# bop_it_sch.net
KiCad netlist of a schematic drawn in Altium Designer
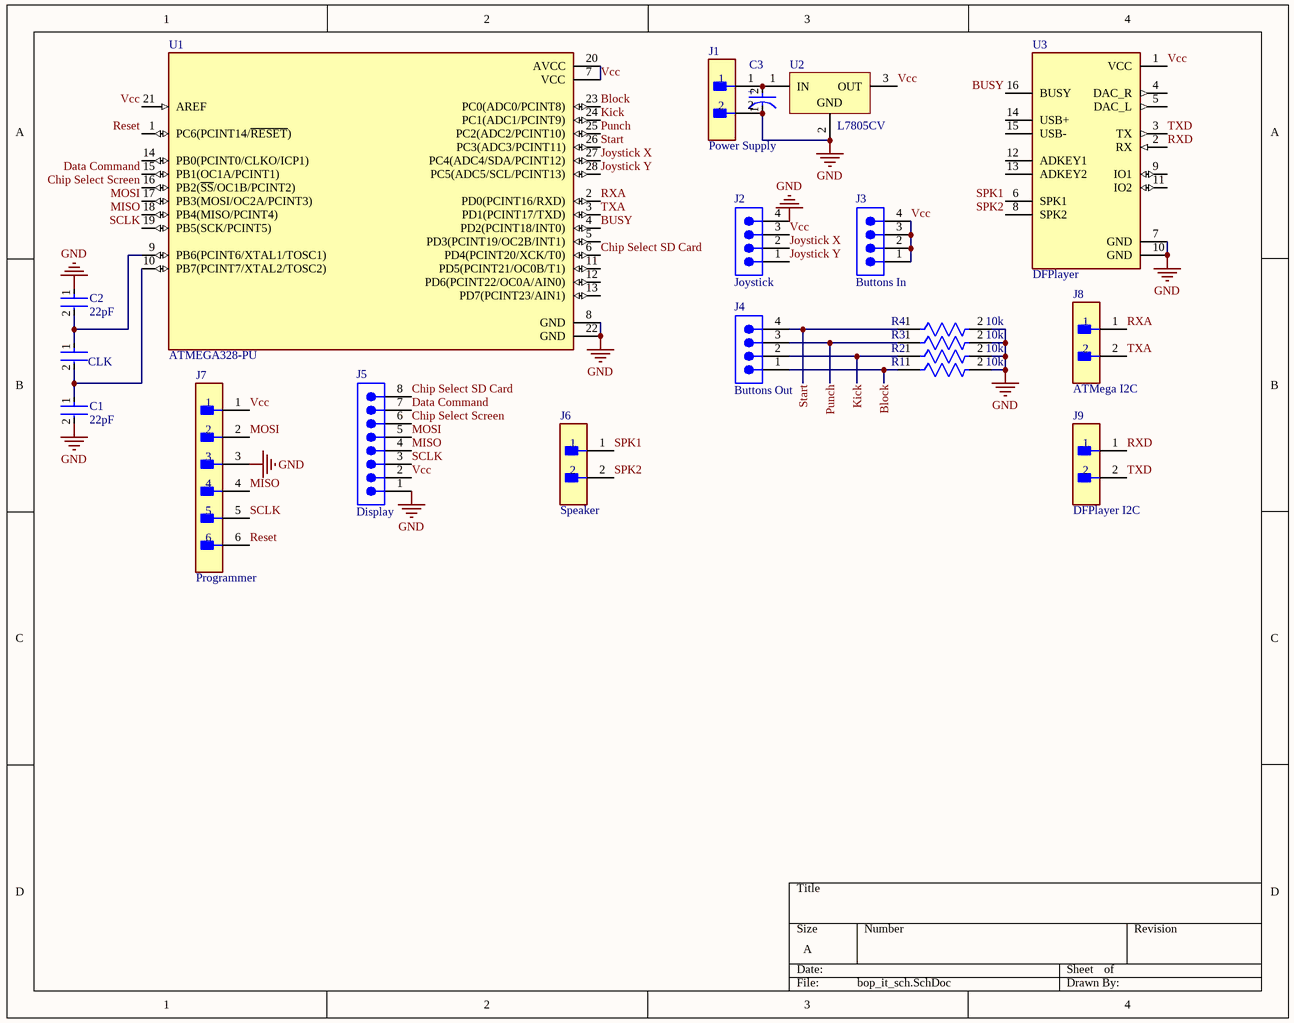
[diagram p0: bop_it_sch.SchDoc]

(export (version "E")
  (design (tool "Eeschema 10.0.6"))
  (components
    (comp (ref "C1")
      (value "22pF")
      (footprint "FP-RDE0M1-MFG")
      (description "Ceramic Capacitor 10nF ±10% 50V X7R Radial")
      (fields (field (name "TOLERANCE") "10%"))
      (libsource (lib "Altium Content Vault") (part "b4654b650e69147ec39a6b967a45e02"))
    )
    (comp (ref "C2")
      (value "22pF")
      (footprint "FP-RDE0M1-MFG")
      (description "Ceramic Capacitor 10nF ±10% 50V X7R Radial")
      (fields (field (name "TOLERANCE") "10%"))
      (libsource (lib "Altium Content Vault") (part "b4654b650e69147ec39a6b967a45e02"))
    )
    (comp (ref "C3")
      (value "~")
      (footprint "FP-RAD-TH-D_5_0_5-L_11_1-MFG")
      (description "Aluminum Electrolytic Capacitors (Radial Lead Type) 1uF ±20% 50V")
      (fields (field (name "TOLERANCE") "20%"))
      (libsource (lib "Altium Content Vault") (part "a00bbbee19879c290e62620ae7e47b1"))
    )
    (comp (ref "CLK")
      (value "~")
      (footprint "FP-RDE0M1-MFG")
      (description "Ceramic Capacitor 10nF ±10% 50V X7R Radial")
      (fields (field (name "TOLERANCE") "10%"))
      (libsource (lib "Altium Content Vault") (part "b4654b650e69147ec39a6b967a45e02"))
    )
    (comp (ref "J1")
      (value "Power Supply")
      (footprint "FP-M20-9990246-MFG")
      (description "CONN HEADER VERT 2POS 2.54MM")
      (fields
        (field (name "OCTOPART") "https://octopart.com/m20-9990246-harwin-2590635")
        (field (name "MANUFACTURER") "Harwin")
      )
      (libsource (lib "Altium Content Vault") (part "3bc925449376181038e59eaffc5286c"))
    )
    (comp (ref "J2")
      (value "Joystick")
      (footprint "61300411121")
      (libsource (lib "Altium Content Vault") (part "Header_Male_1R_04P"))
    )
    (comp (ref "J3")
      (value "Buttons In")
      (footprint "61300411121")
      (libsource (lib "Altium Content Vault") (part "Header_Male_1R_04P"))
    )
    (comp (ref "J4")
      (value "Buttons Out")
      (footprint "61300411121")
      (libsource (lib "Altium Content Vault") (part "Header_Male_1R_04P"))
    )
    (comp (ref "J5")
      (value "Display")
      (footprint "61300811121")
      (libsource (lib "Altium Content Vault") (part "Header_Male_1R_08P"))
    )
    (comp (ref "J6")
      (value "Speaker")
      (footprint "FP-M20-9990246-MFG")
      (description "CONN HEADER VERT 2POS 2.54MM")
      (fields
        (field (name "OCTOPART") "https://octopart.com/m20-9990246-harwin-2590635")
        (field (name "MANUFACTURER") "Harwin")
      )
      (libsource (lib "Altium Content Vault") (part "3bc925449376181038e59eaffc5286c"))
    )
    (comp (ref "J7")
      (value "Programmer")
      (footprint "FP-22-28-4060-MFG")
      (description "CONN HEADER VERT 6POS 2.54MM")
      (libsource (lib "Altium Content Vault") (part "f2cb566baf1c37ab5a3b8e90bbeafd6"))
    )
    (comp (ref "J8")
      (value "ATMega I2C")
      (footprint "FP-M20-9990246-MFG")
      (description "CONN HEADER VERT 2POS 2.54MM")
      (fields
        (field (name "OCTOPART") "https://octopart.com/m20-9990246-harwin-2590635")
        (field (name "MANUFACTURER") "Harwin")
      )
      (libsource (lib "Altium Content Vault") (part "3bc925449376181038e59eaffc5286c"))
    )
    (comp (ref "J9")
      (value "DFPlayer I2C")
      (footprint "FP-M20-9990246-MFG")
      (description "CONN HEADER VERT 2POS 2.54MM")
      (fields
        (field (name "OCTOPART") "https://octopart.com/m20-9990246-harwin-2590635")
        (field (name "MANUFACTURER") "Harwin")
      )
      (libsource (lib "Altium Content Vault") (part "3bc925449376181038e59eaffc5286c"))
    )
    (comp (ref "R1")
      (value "10k")
      (footprint "FP-MBB0207-MFG")
      (description "RES 10K OHM 0.6W 1% AXIAL")
      (fields (field (name "TOLERANCE") "1%"))
      (libsource (lib "Altium Content Vault") (part "1029c3af85768c4190bb7ad29bc67b5"))
    )
    (comp (ref "R2")
      (value "10k")
      (footprint "FP-MBB0207-MFG")
      (description "RES 10K OHM 0.6W 1% AXIAL")
      (fields (field (name "TOLERANCE") "1%"))
      (libsource (lib "Altium Content Vault") (part "1029c3af85768c4190bb7ad29bc67b5"))
    )
    (comp (ref "R3")
      (value "10k")
      (footprint "FP-MBB0207-MFG")
      (description "RES 10K OHM 0.6W 1% AXIAL")
      (fields (field (name "TOLERANCE") "1%"))
      (libsource (lib "Altium Content Vault") (part "1029c3af85768c4190bb7ad29bc67b5"))
    )
    (comp (ref "R4")
      (value "10k")
      (footprint "FP-MBB0207-MFG")
      (description "RES 10K OHM 0.6W 1% AXIAL")
      (fields (field (name "TOLERANCE") "1%"))
      (libsource (lib "Altium Content Vault") (part "1029c3af85768c4190bb7ad29bc67b5"))
    )
    (comp (ref "U1")
      (value "ATMEGA328-PU")
      (footprint "DIP787W46P254L3467H508Q28")
      (description "AVR AVRÂ® ATmega Microcontroller IC 8-Bit 20MHz 32KB (16K x 16) FLASH 28-PDIP")
      (fields (field (name "MF") "Microchip"))
      (libsource (lib "ATMEGA328-PU") (part "ATMEGA328-PU"))
    )
    (comp (ref "U2")
      (value "L7805CV")
      (footprint "TO220FP")
      (description "Positive Voltage Regulator, 5V, 3-Pin TO-220FP")
      (libsource (lib "Altium Content Vault") (part "PM-REG-L4940-SIL3"))
    )
    (comp (ref "U3")
      (value "DFPlayer")
      (footprint "MODULE_DFR0299")
      (description "- MP3 Player Audio Arduino Platform Evaluation Expansion Board")
      (fields (field (name "MF") "DFRobot") (field (name "MP") "DFR0299"))
      (libsource (lib "DFR0299") (part "DFR0299"))
    )
  )
  (nets
    (net (code "1") (name "/BUSY") (class "Default")
      (node (ref "U1") (pin "4") (pinfunction "PD2(PCINT18/INT0)_4") (pintype "bidirectional"))
      (node (ref "U3") (pin "16") (pinfunction "BUSY_16") (pintype "passive"))
    )
    (net (code "2") (name "/Block") (class "Default")
      (node (ref "J4") (pin "1") (pinfunction "1_1") (pintype "passive"))
      (node (ref "R1") (pin "1") (pinfunction "1_1") (pintype "passive"))
      (node (ref "U1") (pin "23") (pinfunction "PC0(ADC0/PCINT8)_23") (pintype "bidirectional"))
    )
    (net (code "3") (name "/Chip Select SD Card") (class "Default")
      (node (ref "J5") (pin "8") (pinfunction "8_8") (pintype "passive"))
      (node (ref "U1") (pin "6") (pinfunction "PD4(PCINT20/XCK/T0)_6") (pintype "bidirectional"))
    )
    (net (code "4") (name "/Chip Select Screen") (class "Default")
      (node (ref "J5") (pin "6") (pinfunction "6_6") (pintype "passive"))
      (node (ref "U1") (pin "16") (pinfunction "PB2(~{SS}/OC1B/PCINT2)_16") (pintype "bidirectional"))
    )
    (net (code "5") (name "/Data Command") (class "Default")
      (node (ref "J5") (pin "7") (pinfunction "7_7") (pintype "passive"))
      (node (ref "U1") (pin "15") (pinfunction "PB1(OC1A/PCINT1)_15") (pintype "bidirectional"))
    )
    (net (code "6") (name "/Joystick X") (class "Default")
      (node (ref "J2") (pin "2") (pinfunction "2_2") (pintype "passive"))
      (node (ref "U1") (pin "27") (pinfunction "PC4(ADC4/SDA/PCINT12)_27") (pintype "bidirectional"))
    )
    (net (code "7") (name "/Joystick Y") (class "Default")
      (node (ref "J2") (pin "1") (pinfunction "1_1") (pintype "passive"))
      (node (ref "U1") (pin "28") (pinfunction "PC5(ADC5/SCL/PCINT13)_28") (pintype "bidirectional"))
    )
    (net (code "8") (name "/Kick") (class "Default")
      (node (ref "J4") (pin "2") (pinfunction "2_2") (pintype "passive"))
      (node (ref "R2") (pin "1") (pinfunction "1_1") (pintype "passive"))
      (node (ref "U1") (pin "24") (pinfunction "PC1(ADC1/PCINT9)_24") (pintype "bidirectional"))
    )
    (net (code "9") (name "/MISO") (class "Default")
      (node (ref "J5") (pin "4") (pinfunction "4_4") (pintype "passive"))
      (node (ref "J7") (pin "4") (pinfunction "4_4") (pintype "passive"))
      (node (ref "U1") (pin "18") (pinfunction "PB4(MISO/PCINT4)_18") (pintype "bidirectional"))
    )
    (net (code "10") (name "/MOSI") (class "Default")
      (node (ref "J5") (pin "5") (pinfunction "5_5") (pintype "passive"))
      (node (ref "J7") (pin "2") (pinfunction "2_2") (pintype "passive"))
      (node (ref "U1") (pin "17") (pinfunction "PB3(MOSI/OC2A/PCINT3)_17") (pintype "bidirectional"))
    )
    (net (code "11") (name "/Punch") (class "Default")
      (node (ref "J4") (pin "3") (pinfunction "3_3") (pintype "passive"))
      (node (ref "R3") (pin "1") (pinfunction "1_1") (pintype "passive"))
      (node (ref "U1") (pin "25") (pinfunction "PC2(ADC2/PCINT10)_25") (pintype "bidirectional"))
    )
    (net (code "12") (name "/RXA") (class "Default")
      (node (ref "J8") (pin "1") (pinfunction "1_1") (pintype "passive"))
      (node (ref "U1") (pin "2") (pinfunction "PD0(PCINT16/RXD)_2") (pintype "bidirectional"))
    )
    (net (code "13") (name "/RXD") (class "Default")
      (node (ref "J9") (pin "1") (pinfunction "1_1") (pintype "passive"))
      (node (ref "U3") (pin "2") (pinfunction "RX_2") (pintype "input"))
    )
    (net (code "14") (name "/Reset") (class "Default")
      (node (ref "J7") (pin "6") (pinfunction "6_6") (pintype "passive"))
      (node (ref "U1") (pin "1") (pinfunction "PC6(PCINT14/~{RESET})_1") (pintype "bidirectional"))
    )
    (net (code "15") (name "/SCLK") (class "Default")
      (node (ref "J5") (pin "3") (pinfunction "3_3") (pintype "passive"))
      (node (ref "J7") (pin "5") (pinfunction "5_5") (pintype "passive"))
      (node (ref "U1") (pin "19") (pinfunction "PB5(SCK/PCINT5)_19") (pintype "bidirectional"))
    )
    (net (code "16") (name "/SPK1") (class "Default")
      (node (ref "J6") (pin "1") (pinfunction "1_1") (pintype "passive"))
      (node (ref "U3") (pin "6") (pinfunction "SPK1_6") (pintype "passive"))
    )
    (net (code "17") (name "/SPK2") (class "Default")
      (node (ref "J6") (pin "2") (pinfunction "2_2") (pintype "passive"))
      (node (ref "U3") (pin "8") (pinfunction "SPK2_8") (pintype "passive"))
    )
    (net (code "18") (name "/Start") (class "Default")
      (node (ref "J4") (pin "4") (pinfunction "4_4") (pintype "passive"))
      (node (ref "R4") (pin "1") (pinfunction "1_1") (pintype "passive"))
      (node (ref "U1") (pin "26") (pinfunction "PC3(ADC3/PCINT11)_26") (pintype "bidirectional"))
    )
    (net (code "19") (name "/TXA") (class "Default")
      (node (ref "J8") (pin "2") (pinfunction "2_2") (pintype "passive"))
      (node (ref "U1") (pin "3") (pinfunction "PD1(PCINT17/TXD)_3") (pintype "bidirectional"))
    )
    (net (code "20") (name "/TXD") (class "Default")
      (node (ref "J9") (pin "2") (pinfunction "2_2") (pintype "passive"))
      (node (ref "U3") (pin "3") (pinfunction "TX_3") (pintype "output"))
    )
    (net (code "21") (name "/Vcc") (class "Default")
      (node (ref "J2") (pin "3") (pinfunction "3_3") (pintype "passive"))
      (node (ref "J3") (pin "1") (pinfunction "1_1") (pintype "passive"))
      (node (ref "J3") (pin "2") (pinfunction "2_2") (pintype "passive"))
      (node (ref "J3") (pin "3") (pinfunction "3_3") (pintype "passive"))
      (node (ref "J3") (pin "4") (pinfunction "4_4") (pintype "passive"))
      (node (ref "J5") (pin "2") (pinfunction "2_2") (pintype "passive"))
      (node (ref "J7") (pin "1") (pinfunction "1_1") (pintype "passive"))
      (node (ref "U1") (pin "20") (pinfunction "AVCC_20") (pintype "power_in"))
      (node (ref "U1") (pin "21") (pinfunction "AREF_21") (pintype "input"))
      (node (ref "U1") (pin "7") (pinfunction "VCC_7") (pintype "power_in"))
      (node (ref "U2") (pin "3") (pinfunction "OUT_3") (pintype "power_in"))
      (node (ref "U3") (pin "1") (pinfunction "VCC_1") (pintype "power_in"))
    )
    (net (code "22") (name "GND") (class "Default")
      (node (ref "C1") (pin "2") (pinfunction "2_2") (pintype "passive"))
      (node (ref "C2") (pin "1") (pinfunction "1_1") (pintype "passive"))
      (node (ref "C3") (pin "1") (pinfunction "C_1") (pintype "passive"))
      (node (ref "J1") (pin "2") (pinfunction "2_2") (pintype "passive"))
      (node (ref "J2") (pin "4") (pinfunction "4_4") (pintype "passive"))
      (node (ref "J5") (pin "1") (pinfunction "1_1") (pintype "passive"))
      (node (ref "J7") (pin "3") (pinfunction "3_3") (pintype "passive"))
      (node (ref "R1") (pin "2") (pinfunction "2_2") (pintype "passive"))
      (node (ref "R2") (pin "2") (pinfunction "2_2") (pintype "passive"))
      (node (ref "R3") (pin "2") (pinfunction "2_2") (pintype "passive"))
      (node (ref "R4") (pin "2") (pinfunction "2_2") (pintype "passive"))
      (node (ref "U1") (pin "22") (pinfunction "GND_22") (pintype "power_in"))
      (node (ref "U1") (pin "8") (pinfunction "GND_8") (pintype "power_in"))
      (node (ref "U2") (pin "2") (pinfunction "GND_2") (pintype "power_in"))
      (node (ref "U3") (pin "10") (pinfunction "GND_10") (pintype "power_in"))
      (node (ref "U3") (pin "7") (pinfunction "GND_7") (pintype "power_in"))
    )
    (net (code "23") (name "Net-(C3-A)") (class "Default")
      (node (ref "C3") (pin "2") (pinfunction "A_2") (pintype "passive"))
      (node (ref "J1") (pin "1") (pinfunction "1_1") (pintype "passive"))
      (node (ref "U2") (pin "1") (pinfunction "IN_1") (pintype "power_in"))
    )
    (net (code "24") (name "Net-(U1-PB6(PCINT6{slash}XTAL1{slash}TOSC1))") (class "Default")
      (node (ref "C2") (pin "2") (pinfunction "2_2") (pintype "passive"))
      (node (ref "CLK") (pin "1") (pinfunction "1_1") (pintype "passive"))
      (node (ref "U1") (pin "9") (pinfunction "PB6(PCINT6/XTAL1/TOSC1)_9") (pintype "bidirectional"))
    )
    (net (code "25") (name "Net-(U1-PB7(PCINT7{slash}XTAL2{slash}TOSC2))") (class "Default")
      (node (ref "C1") (pin "1") (pinfunction "1_1") (pintype "passive"))
      (node (ref "CLK") (pin "2") (pinfunction "2_2") (pintype "passive"))
      (node (ref "U1") (pin "10") (pinfunction "PB7(PCINT7/XTAL2/TOSC2)_10") (pintype "bidirectional"))
    )
    (net (code "26") (name "unconnected-(U1-PB0(PCINT0{slash}CLKO{slash}ICP1)-Pad14)") (class "Default")
      (node (ref "U1") (pin "14") (pinfunction "PB0(PCINT0/CLKO/ICP1)_14") (pintype "bidirectional"))
    )
    (net (code "27") (name "unconnected-(U1-PD3(PCINT19{slash}OC2B{slash}INT1)-Pad5)") (class "Default")
      (node (ref "U1") (pin "5") (pinfunction "PD3(PCINT19/OC2B/INT1)_5") (pintype "bidirectional"))
    )
    (net (code "28") (name "unconnected-(U1-PD5(PCINT21{slash}OC0B{slash}T1)-Pad11)") (class "Default")
      (node (ref "U1") (pin "11") (pinfunction "PD5(PCINT21/OC0B/T1)_11") (pintype "bidirectional"))
    )
    (net (code "29") (name "unconnected-(U1-PD6(PCINT22{slash}OC0A{slash}AIN0)-Pad12)") (class "Default")
      (node (ref "U1") (pin "12") (pinfunction "PD6(PCINT22/OC0A/AIN0)_12") (pintype "bidirectional"))
    )
    (net (code "30") (name "unconnected-(U1-PD7(PCINT23{slash}AIN1)-Pad13)") (class "Default")
      (node (ref "U1") (pin "13") (pinfunction "PD7(PCINT23/AIN1)_13") (pintype "bidirectional"))
    )
    (net (code "31") (name "unconnected-(U3-ADKEY1-Pad12)") (class "Default")
      (node (ref "U3") (pin "12") (pinfunction "ADKEY1_12") (pintype "passive"))
    )
    (net (code "32") (name "unconnected-(U3-ADKEY2-Pad13)") (class "Default")
      (node (ref "U3") (pin "13") (pinfunction "ADKEY2_13") (pintype "passive"))
    )
    (net (code "33") (name "unconnected-(U3-DAC_L-Pad5)") (class "Default")
      (node (ref "U3") (pin "5") (pinfunction "DAC_L_5") (pintype "output"))
    )
    (net (code "34") (name "unconnected-(U3-DAC_R-Pad4)") (class "Default")
      (node (ref "U3") (pin "4") (pinfunction "DAC_R_4") (pintype "output"))
    )
    (net (code "35") (name "unconnected-(U3-IO1-Pad9)") (class "Default")
      (node (ref "U3") (pin "9") (pinfunction "IO1_9") (pintype "bidirectional"))
    )
    (net (code "36") (name "unconnected-(U3-IO2-Pad11)") (class "Default")
      (node (ref "U3") (pin "11") (pinfunction "IO2_11") (pintype "bidirectional"))
    )
    (net (code "37") (name "unconnected-(U3-USB+-Pad14)") (class "Default")
      (node (ref "U3") (pin "14") (pinfunction "USB+_14") (pintype "passive"))
    )
    (net (code "38") (name "unconnected-(U3-USB--Pad15)") (class "Default")
      (node (ref "U3") (pin "15") (pinfunction "USB-_15") (pintype "passive"))
    )
  )
)
